# temp-accel-chain.net
KiCad netlist of a schematic drawn in EAGLE
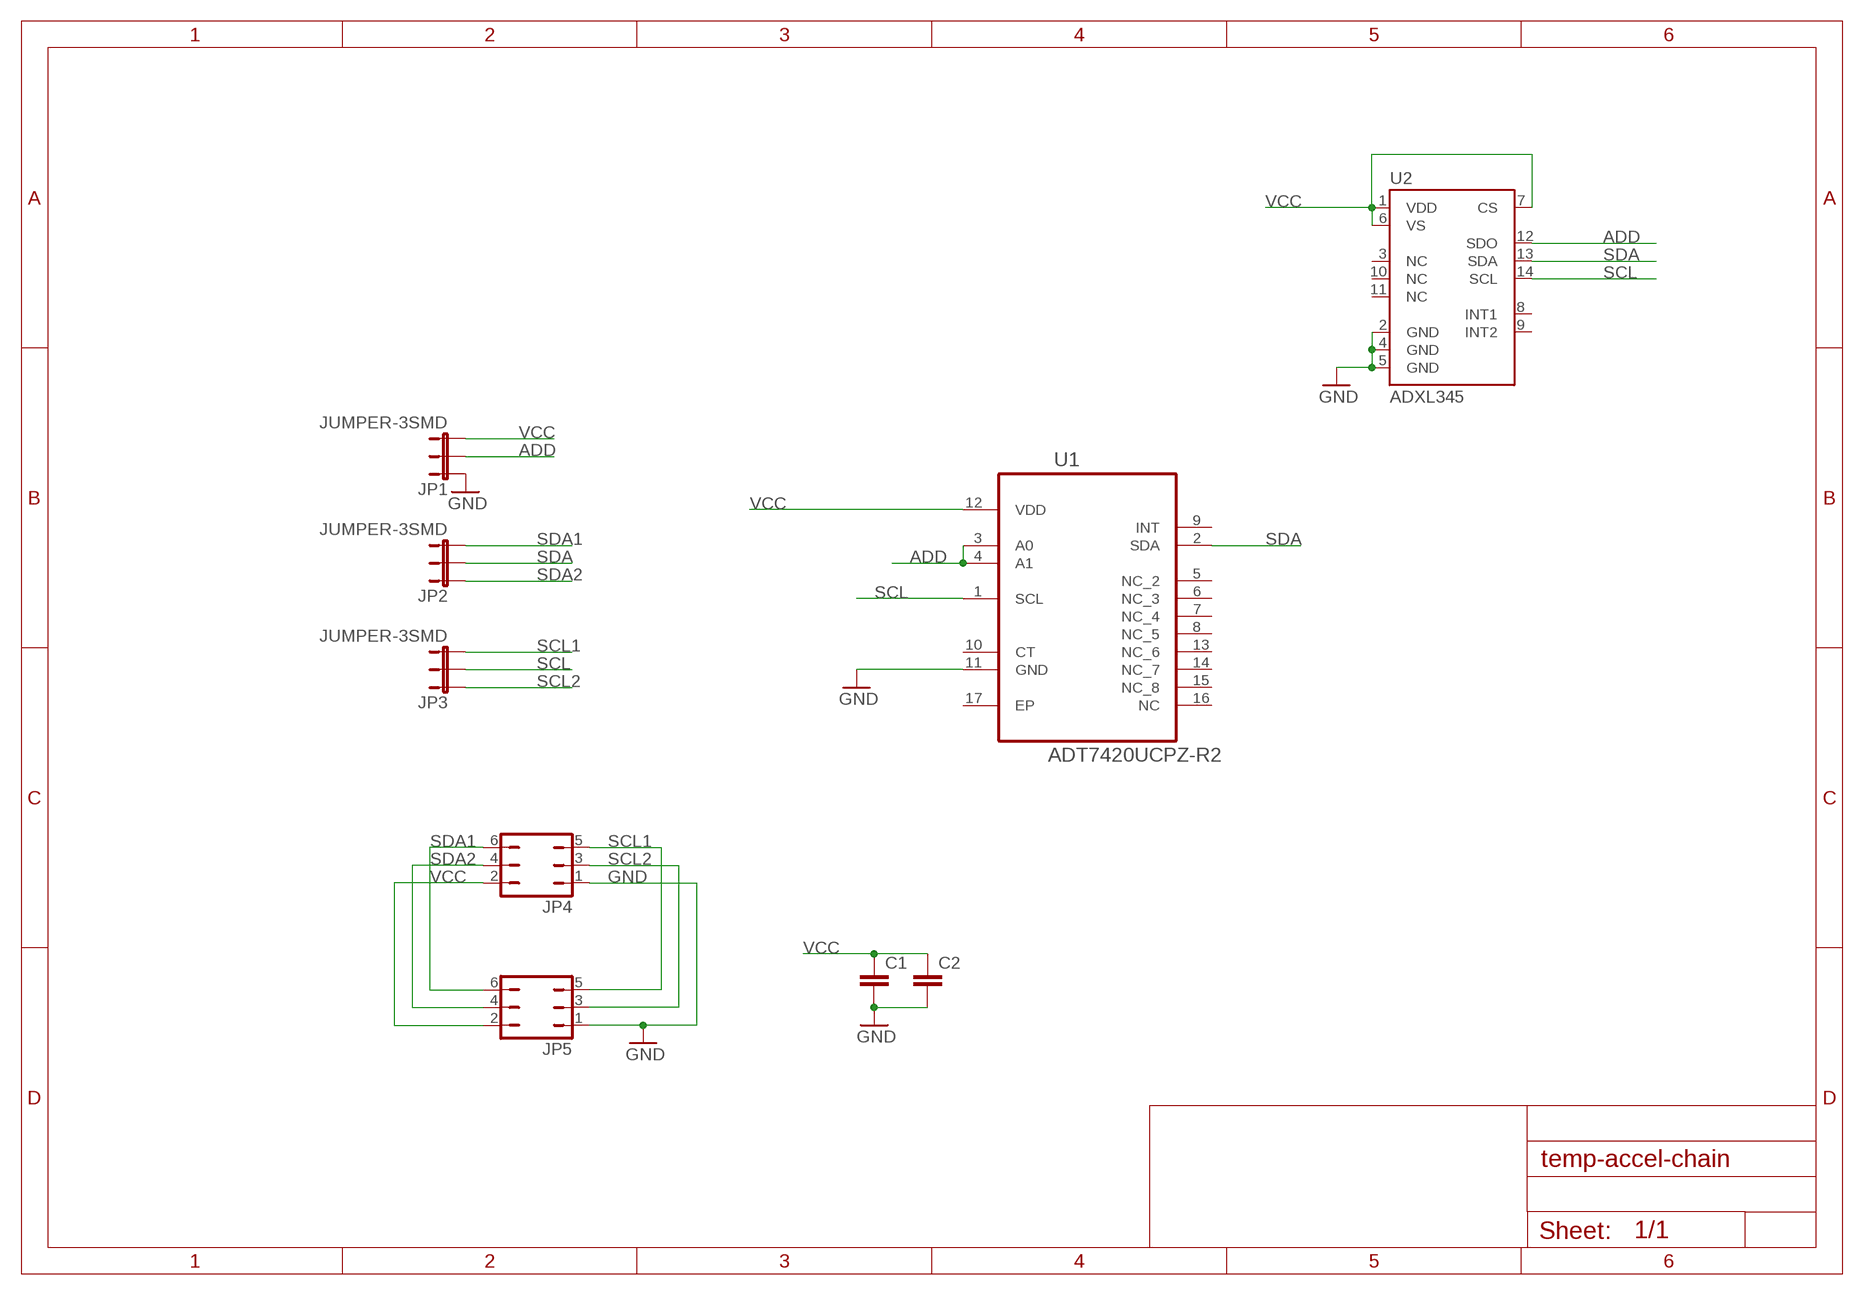
[diagram p0: schematic, sheet 1]

(export (version "E")
  (design (tool "Eeschema 10.0.6"))
  (components
    (comp (ref "C1")
      (value "C-EUC0805")
      (footprint "eagle-import:C0805")
      (libsource (lib "eagle-import") (part "C-EUC0805"))
    )
    (comp (ref "C2")
      (value "C-EUC0805")
      (footprint "eagle-import:C0805")
      (libsource (lib "eagle-import") (part "C-EUC0805"))
    )
    (comp (ref "JP1")
      (value "JUMPER-3SMD")
      (footprint "eagle-import:SJ_3")
      (libsource (lib "eagle-import") (part "JUMPER-3SMD"))
    )
    (comp (ref "JP2")
      (value "JUMPER-3SMD")
      (footprint "eagle-import:SJ_3")
      (libsource (lib "eagle-import") (part "JUMPER-3SMD"))
    )
    (comp (ref "JP3")
      (value "JUMPER-3SMD")
      (footprint "eagle-import:SJ_3")
      (libsource (lib "eagle-import") (part "JUMPER-3SMD"))
    )
    (comp (ref "JP4")
      (value "JP3Q")
      (footprint "eagle-import:JP3Q")
      (libsource (lib "eagle-import") (part "JP3Q"))
    )
    (comp (ref "JP5")
      (value "JP3Q")
      (footprint "eagle-import:JP3Q")
      (libsource (lib "eagle-import") (part "JP3Q"))
    )
    (comp (ref "U1")
      (value "ADT7420UCPZ-R2")
      (footprint "eagle-import:QFN65P400X400X80-17N")
      (libsource (lib "eagle-import") (part "ADT7420UCPZ-R2"))
    )
    (comp (ref "U2")
      (value "ADXL345")
      (footprint "eagle-import:LGA14")
      (libsource (lib "eagle-import") (part "ADXL345"))
    )
  )
  (nets
    (net (code "1") (name "/ADD") (class "Default")
      (node (ref "JP1") (pin "2") (pinfunction "2_2") (pintype "passive"))
      (node (ref "U1") (pin "3") (pinfunction "A0_3") (pintype "input"))
      (node (ref "U1") (pin "4") (pinfunction "A1_4") (pintype "input"))
      (node (ref "U2") (pin "12") (pinfunction "SDO_12") (pintype "bidirectional"))
    )
    (net (code "2") (name "/SCL") (class "Default")
      (node (ref "JP3") (pin "2") (pinfunction "2_2") (pintype "passive"))
      (node (ref "U1") (pin "1") (pinfunction "SCL_1") (pintype "input"))
      (node (ref "U2") (pin "14") (pinfunction "SCL_14") (pintype "bidirectional"))
    )
    (net (code "3") (name "/SCL1") (class "Default")
      (node (ref "JP3") (pin "3") (pinfunction "3_3") (pintype "passive"))
      (node (ref "JP4") (pin "5") (pinfunction "5_5") (pintype "passive"))
      (node (ref "JP5") (pin "5") (pinfunction "5_5") (pintype "passive"))
    )
    (net (code "4") (name "/SCL2") (class "Default")
      (node (ref "JP3") (pin "1") (pinfunction "1_1") (pintype "passive"))
      (node (ref "JP4") (pin "3") (pinfunction "3_3") (pintype "passive"))
      (node (ref "JP5") (pin "3") (pinfunction "3_3") (pintype "passive"))
    )
    (net (code "5") (name "/SDA") (class "Default")
      (node (ref "JP2") (pin "2") (pinfunction "2_2") (pintype "passive"))
      (node (ref "U1") (pin "2") (pinfunction "SDA_2") (pintype "output"))
      (node (ref "U2") (pin "13") (pinfunction "SDA_13") (pintype "bidirectional"))
    )
    (net (code "6") (name "/SDA1") (class "Default")
      (node (ref "JP2") (pin "3") (pinfunction "3_3") (pintype "passive"))
      (node (ref "JP4") (pin "6") (pinfunction "6_6") (pintype "passive"))
      (node (ref "JP5") (pin "6") (pinfunction "6_6") (pintype "passive"))
    )
    (net (code "7") (name "/SDA2") (class "Default")
      (node (ref "JP2") (pin "1") (pinfunction "1_1") (pintype "passive"))
      (node (ref "JP4") (pin "4") (pinfunction "4_4") (pintype "passive"))
      (node (ref "JP5") (pin "4") (pinfunction "4_4") (pintype "passive"))
    )
    (net (code "8") (name "/VCC") (class "Default")
      (node (ref "C1") (pin "1") (pinfunction "1_1") (pintype "passive"))
      (node (ref "C2") (pin "1") (pinfunction "1_1") (pintype "passive"))
      (node (ref "JP1") (pin "3") (pinfunction "3_3") (pintype "passive"))
      (node (ref "JP4") (pin "2") (pinfunction "2_2") (pintype "passive"))
      (node (ref "JP5") (pin "2") (pinfunction "2_2") (pintype "passive"))
      (node (ref "U1") (pin "12") (pinfunction "VDD_12") (pintype "power_in"))
      (node (ref "U2") (pin "1") (pinfunction "VDD_1") (pintype "bidirectional"))
      (node (ref "U2") (pin "6") (pinfunction "VS_6") (pintype "bidirectional"))
      (node (ref "U2") (pin "7") (pinfunction "CS_7") (pintype "bidirectional"))
    )
    (net (code "9") (name "GND") (class "Default")
      (node (ref "C1") (pin "2") (pinfunction "2_2") (pintype "passive"))
      (node (ref "C2") (pin "2") (pinfunction "2_2") (pintype "passive"))
      (node (ref "JP1") (pin "1") (pinfunction "1_1") (pintype "passive"))
      (node (ref "JP4") (pin "1") (pinfunction "1_1") (pintype "passive"))
      (node (ref "JP5") (pin "1") (pinfunction "1_1") (pintype "passive"))
      (node (ref "U1") (pin "11") (pinfunction "GND_11") (pintype "passive"))
      (node (ref "U2") (pin "2") (pinfunction "GND_2") (pintype "bidirectional"))
      (node (ref "U2") (pin "4") (pinfunction "GND_4") (pintype "bidirectional"))
      (node (ref "U2") (pin "5") (pinfunction "GND_5") (pintype "bidirectional"))
    )
    (net (code "10") (name "unconnected-(U1-CT-Pad10)") (class "Default")
      (node (ref "U1") (pin "10") (pinfunction "CT_10") (pintype "input"))
    )
    (net (code "11") (name "unconnected-(U1-EP-Pad17)") (class "Default")
      (node (ref "U1") (pin "17") (pinfunction "EP_17") (pintype "passive"))
    )
    (net (code "12") (name "unconnected-(U1-INT-Pad9)") (class "Default")
      (node (ref "U1") (pin "9") (pinfunction "INT_9") (pintype "output"))
    )
    (net (code "13") (name "unconnected-(U1-NC-Pad16)") (class "Default")
      (node (ref "U1") (pin "16") (pinfunction "NC_16") (pintype "no_connect"))
    )
    (net (code "14") (name "unconnected-(U1-NC_2-Pad5)") (class "Default")
      (node (ref "U1") (pin "5") (pinfunction "NC_2_5") (pintype "no_connect"))
    )
    (net (code "15") (name "unconnected-(U1-NC_3-Pad6)") (class "Default")
      (node (ref "U1") (pin "6") (pinfunction "NC_3_6") (pintype "no_connect"))
    )
    (net (code "16") (name "unconnected-(U1-NC_4-Pad7)") (class "Default")
      (node (ref "U1") (pin "7") (pinfunction "NC_4_7") (pintype "no_connect"))
    )
    (net (code "17") (name "unconnected-(U1-NC_5-Pad8)") (class "Default")
      (node (ref "U1") (pin "8") (pinfunction "NC_5_8") (pintype "no_connect"))
    )
    (net (code "18") (name "unconnected-(U1-NC_6-Pad13)") (class "Default")
      (node (ref "U1") (pin "13") (pinfunction "NC_6_13") (pintype "no_connect"))
    )
    (net (code "19") (name "unconnected-(U1-NC_7-Pad14)") (class "Default")
      (node (ref "U1") (pin "14") (pinfunction "NC_7_14") (pintype "no_connect"))
    )
    (net (code "20") (name "unconnected-(U1-NC_8-Pad15)") (class "Default")
      (node (ref "U1") (pin "15") (pinfunction "NC_8_15") (pintype "no_connect"))
    )
    (net (code "21") (name "unconnected-(U2-INT1-Pad8)") (class "Default")
      (node (ref "U2") (pin "8") (pinfunction "INT1_8") (pintype "bidirectional"))
    )
    (net (code "22") (name "unconnected-(U2-INT2-Pad9)") (class "Default")
      (node (ref "U2") (pin "9") (pinfunction "INT2_9") (pintype "bidirectional"))
    )
    (net (code "23") (name "unconnected-(U2-NC-Pad3)") (class "Default")
      (node (ref "U2") (pin "3") (pinfunction "NC_3") (pintype "bidirectional"))
    )
    (net (code "24") (name "unconnected-(U2-NC-Pad10)") (class "Default")
      (node (ref "U2") (pin "10") (pinfunction "NC_10") (pintype "bidirectional"))
    )
    (net (code "25") (name "unconnected-(U2-NC-Pad11)") (class "Default")
      (node (ref "U2") (pin "11") (pinfunction "NC_11") (pintype "bidirectional"))
    )
  )
)
